# design.net
KiCad netlist of a schematic drawn in Altium Designer
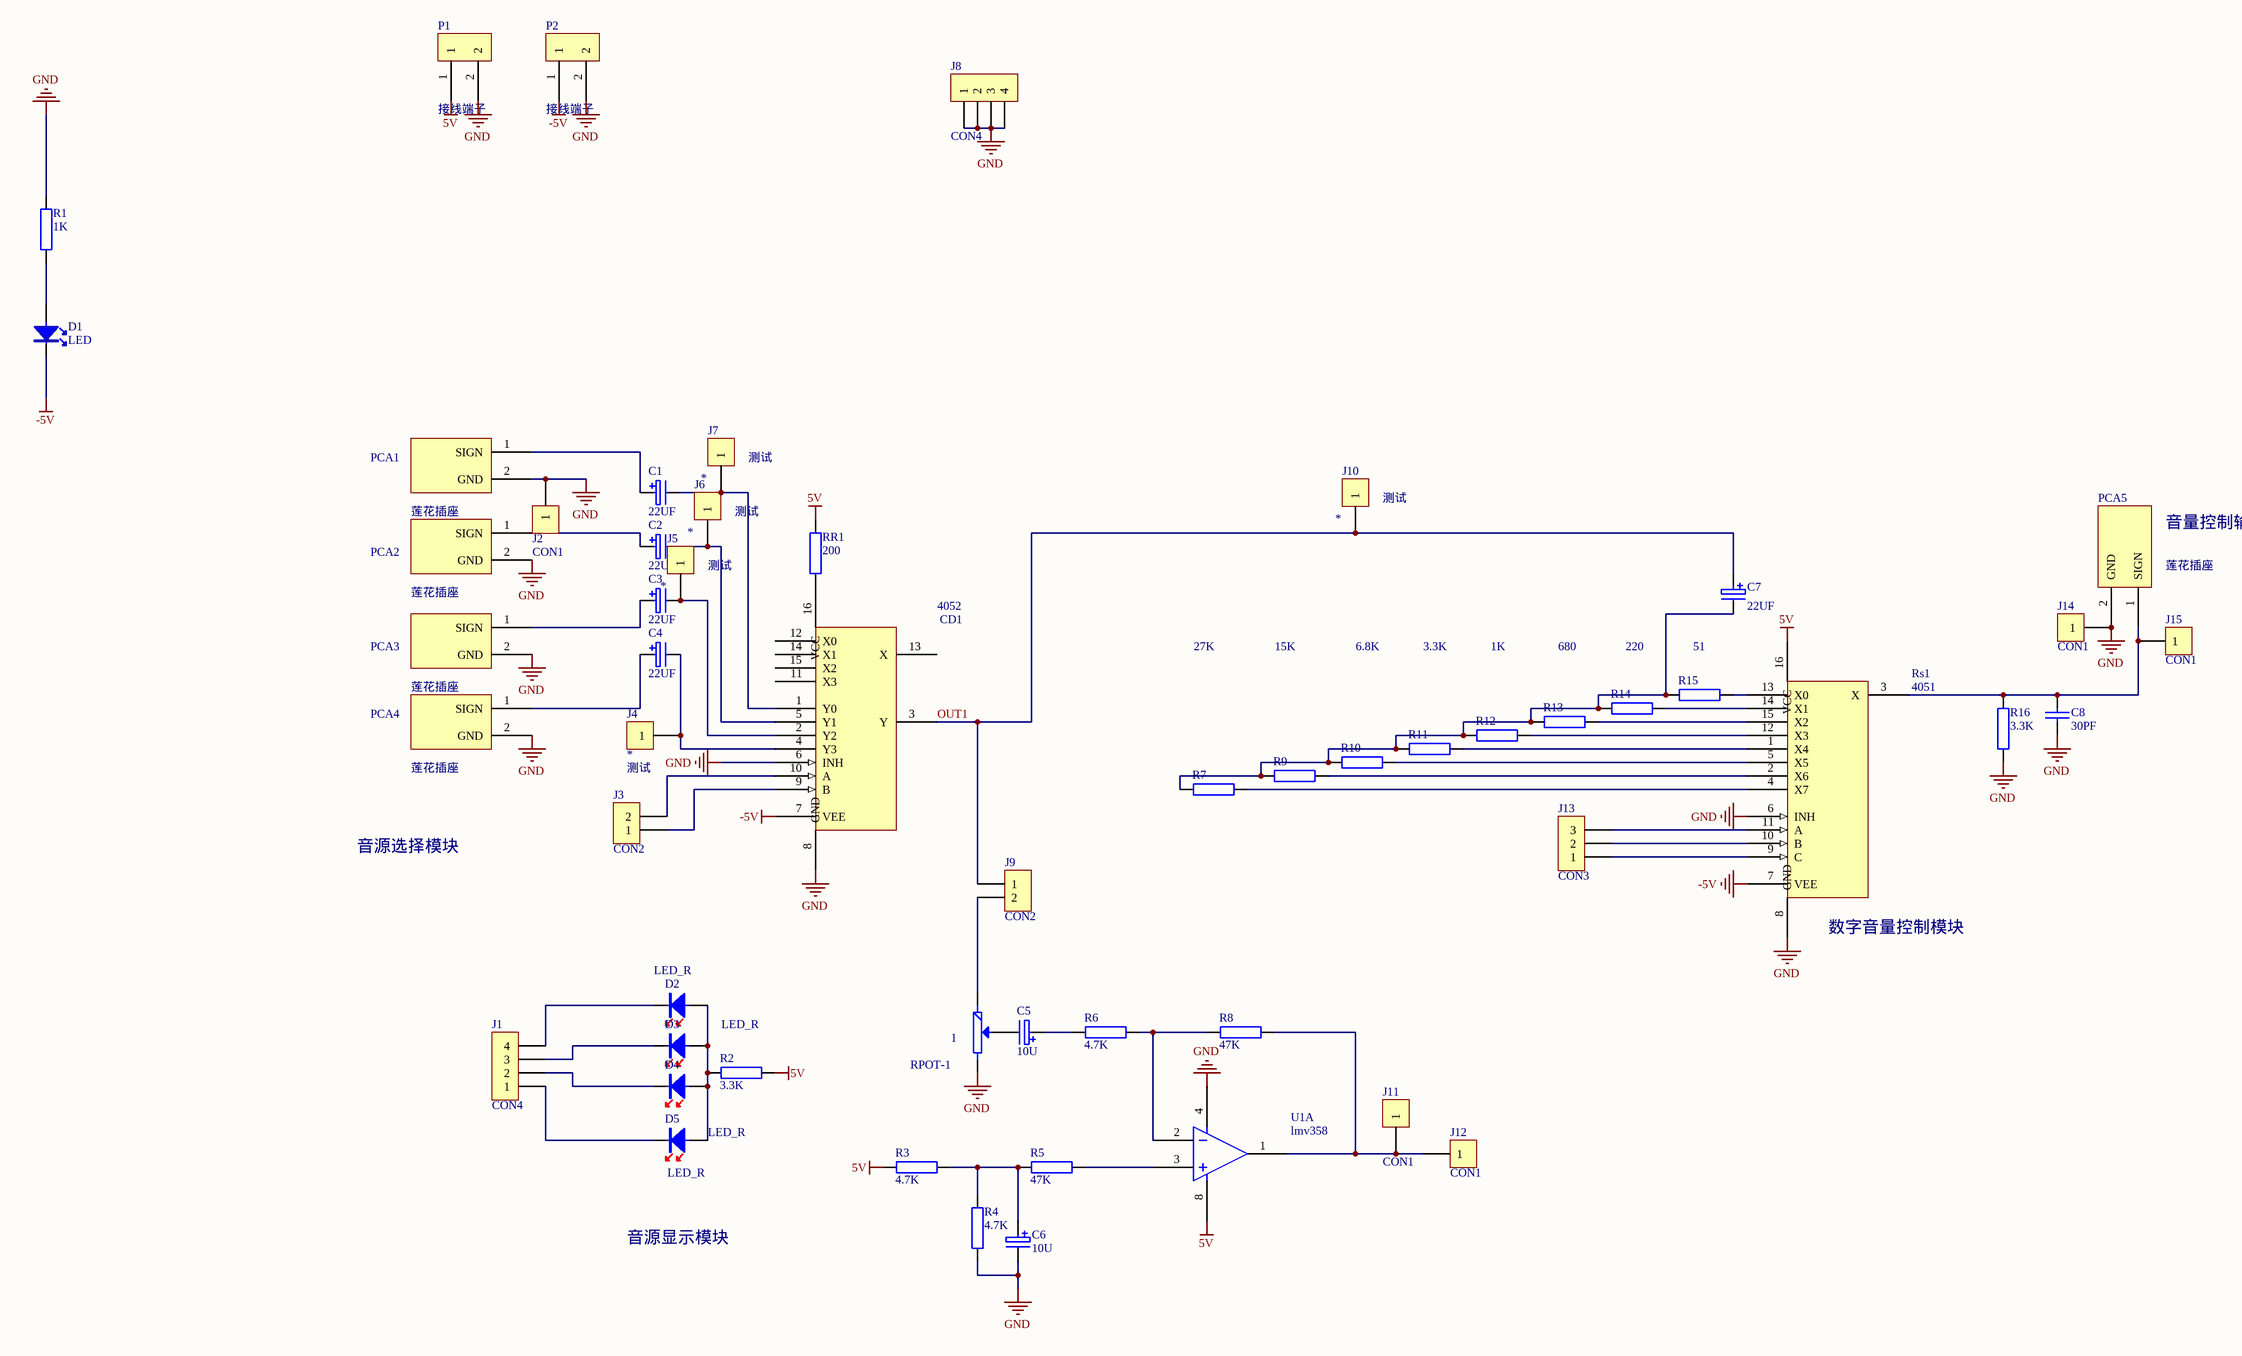
[diagram p0: 开关部分.SchDoc]

(export (version "E")
  (design (tool "Eeschema 10.0.6"))
  (components
    (comp (ref "1")
      (value "RPOT-1")
      (footprint "RVR-2")
      (description "普通电位器")
      (libsource (lib "电阻") (part "RPOT-1"))
    )
    (comp (ref "C1") (value "22UF") (footprint "CAO2") (libsource (lib "电容") (part "CAP3")))
    (comp (ref "C2") (value "22UF") (footprint "CAO2") (libsource (lib "电容") (part "CAP3")))
    (comp (ref "C3") (value "22UF") (footprint "CAO2") (libsource (lib "电容") (part "CAP3")))
    (comp (ref "C4") (value "22UF") (footprint "CAO2") (libsource (lib "电容") (part "CAP3")))
    (comp (ref "C5") (value "10U") (footprint "CAO1") (libsource (lib "电容") (part "CAP3")))
    (comp (ref "C6") (value "10U") (footprint "CAO1") (libsource (lib "电容") (part "CAP3")))
    (comp (ref "C7") (value "22UF") (footprint "CAO2") (libsource (lib "电容") (part "CAP3")))
    (comp (ref "C8") (value "30PF") (footprint "CAP2") (libsource (lib "电容") (part "CAP1")))
    (comp (ref "CD1") (value "4052") (footprint "SO-16") (libsource (lib "51库") (part "4052")))
    (comp (ref "D1") (value "LED") (footprint "LED2_B") (libsource (lib "二极管") (part "LED")))
    (comp (ref "D2") (value "LED_R") (footprint "LED2_B") (libsource (lib "Diode二极管") (part "LED_R")))
    (comp (ref "D3") (value "LED_R") (footprint "LED2_B") (libsource (lib "Diode二极管") (part "LED_R")))
    (comp (ref "D4") (value "LED_R") (footprint "LED2_B") (libsource (lib "Diode二极管") (part "LED_R")))
    (comp (ref "D5") (value "LED_R") (footprint "LED2_B") (libsource (lib "Diode二极管") (part "LED_R")))
    (comp (ref "J1")
      (value "CON4")
      (footprint "sip-4")
      (description "Connector")
      (libsource (lib "") (part "CON4_1"))
    )
    (comp (ref "J2")
      (value "CON1")
      (footprint "SIP-1")
      (description "Connector")
      (libsource (lib "排针") (part "测试"))
    )
    (comp (ref "J3")
      (value "CON2")
      (footprint "sip-2")
      (description "Connector")
      (libsource (lib "排针") (part "CON2"))
    )
    (comp (ref "J4")
      (value "*")
      (footprint "SIP-1")
      (description "Connector")
      (fields (field (name "测试") "测试"))
      (libsource (lib "") (part "CON1_2"))
    )
    (comp (ref "J5")
      (value "*")
      (footprint "SIP-1")
      (description "Connector")
      (fields (field (name "测试") "测试"))
      (libsource (lib "排针") (part "CON1"))
    )
    (comp (ref "J6")
      (value "*")
      (footprint "SIP-1")
      (description "Connector")
      (fields (field (name "测试") "测试"))
      (libsource (lib "排针") (part "CON1"))
    )
    (comp (ref "J7")
      (value "*")
      (footprint "SIP-1")
      (description "Connector")
      (fields (field (name "测试") "测试"))
      (libsource (lib "排针") (part "CON1"))
    )
    (comp (ref "J8")
      (value "CON4")
      (footprint "sip-4")
      (description "Connector")
      (libsource (lib "排针") (part "CON4"))
    )
    (comp (ref "J9")
      (value "CON2")
      (footprint "sip-2")
      (description "Connector")
      (libsource (lib "") (part "CON2_1"))
    )
    (comp (ref "J10")
      (value "*")
      (footprint "SIP-1")
      (description "Connector")
      (fields (field (name "测试") "测试"))
      (libsource (lib "排针") (part "CON1"))
    )
    (comp (ref "J11")
      (value "CON1")
      (footprint "SIP-1")
      (description "Connector")
      (libsource (lib "排针") (part "CON1"))
    )
    (comp (ref "J12")
      (value "CON1")
      (footprint "SIP-1")
      (description "Connector")
      (libsource (lib "") (part "CON1_1"))
    )
    (comp (ref "J13")
      (value "CON3")
      (footprint "sip-3")
      (description "Connector")
      (libsource (lib "排针") (part "CON3"))
    )
    (comp (ref "J14")
      (value "CON1")
      (footprint "SIP-1")
      (description "Connector")
      (libsource (lib "") (part "CON1_2"))
    )
    (comp (ref "J15")
      (value "CON1")
      (footprint "SIP-1")
      (description "Connector")
      (libsource (lib "") (part "CON1_1"))
    )
    (comp (ref "P1") (value "接线端子") (footprint "音频功放自画库:接线端子") (libsource (lib "音频功放自画库") (part "接线端子")))
    (comp (ref "P2") (value "接线端子") (footprint "音频功放自画库:接线端子") (libsource (lib "音频功放自画库") (part "接线端子")))
    (comp (ref "PCA1") (value "莲花插座") (footprint "莲花母座") (libsource (lib "音频功放自画库") (part "PCA")))
    (comp (ref "PCA2") (value "莲花插座") (footprint "莲花母座") (libsource (lib "音频功放自画库") (part "PCA")))
    (comp (ref "PCA3") (value "莲花插座") (footprint "莲花母座") (libsource (lib "音频功放自画库") (part "PCA")))
    (comp (ref "PCA4") (value "莲花插座") (footprint "莲花母座") (libsource (lib "音频功放自画库") (part "PCA")))
    (comp (ref "PCA5") (value "莲花插座") (footprint "莲花母座") (libsource (lib "") (part "PCA_1")))
    (comp (ref "R1")
      (value "1K")
      (footprint "AXIAL0.4")
      (description "电阻")
      (libsource (lib "电阻") (part "RES"))
    )
    (comp (ref "R2")
      (value "3.3K")
      (footprint "AXIAL0.4")
      (description "电阻")
      (libsource (lib "电阻") (part "RES"))
    )
    (comp (ref "R3")
      (value "4.7K")
      (footprint "AXIAL0.4")
      (description "电阻")
      (libsource (lib "电阻") (part "RES"))
    )
    (comp (ref "R4")
      (value "4.7K")
      (footprint "AXIAL0.4")
      (description "电阻")
      (libsource (lib "电阻") (part "RES"))
    )
    (comp (ref "R5")
      (value "47K")
      (footprint "AXIAL0.4")
      (description "电阻")
      (libsource (lib "电阻") (part "RES"))
    )
    (comp (ref "R6")
      (value "4.7K")
      (footprint "AXIAL0.4")
      (description "电阻")
      (libsource (lib "电阻") (part "RES"))
    )
    (comp (ref "R7")
      (value "27K")
      (footprint "AXIAL0.4")
      (description "电阻")
      (libsource (lib "电阻") (part "RES"))
    )
    (comp (ref "R8")
      (value "47K")
      (footprint "AXIAL0.4")
      (description "电阻")
      (libsource (lib "电阻") (part "RES"))
    )
    (comp (ref "R9")
      (value "15K")
      (footprint "AXIAL0.4")
      (description "电阻")
      (libsource (lib "电阻") (part "RES"))
    )
    (comp (ref "R10")
      (value "6.8K")
      (footprint "AXIAL0.4")
      (description "电阻")
      (libsource (lib "电阻") (part "RES"))
    )
    (comp (ref "R11")
      (value "3.3K")
      (footprint "AXIAL0.4")
      (description "电阻")
      (libsource (lib "电阻") (part "RES"))
    )
    (comp (ref "R12")
      (value "1K")
      (footprint "AXIAL0.4")
      (description "电阻")
      (libsource (lib "电阻") (part "RES"))
    )
    (comp (ref "R13")
      (value "680")
      (footprint "AXIAL0.4")
      (description "电阻")
      (libsource (lib "电阻") (part "RES"))
    )
    (comp (ref "R14")
      (value "220")
      (footprint "AXIAL0.4")
      (description "电阻")
      (libsource (lib "电阻") (part "RES"))
    )
    (comp (ref "R15")
      (value "51")
      (footprint "AXIAL0.4")
      (description "电阻")
      (libsource (lib "电阻") (part "RES"))
    )
    (comp (ref "R16")
      (value "3.3K")
      (footprint "AXIAL0.4")
      (description "电阻")
      (libsource (lib "电阻") (part "RES"))
    )
    (comp (ref "RR1")
      (value "200")
      (footprint "AXIAL0.4")
      (description "电阻")
      (libsource (lib "电阻") (part "RES"))
    )
    (comp (ref "Rs1") (value "4051") (footprint "SO-16") (libsource (lib "51库") (part "4051")))
    (comp (ref "U1") (value "lmv358") (footprint "SOP8") (libsource (lib "运放") (part "NE5532")))
  )
  (nets
    (net (code "1") (name "-5V") (class "Default")
      (node (ref "CD1") (pin "7") (pinfunction "VEE_7") (pintype "passive"))
      (node (ref "D1") (pin "2") (pinfunction "2_2") (pintype "passive"))
      (node (ref "P2") (pin "1") (pinfunction "1_1") (pintype "passive"))
      (node (ref "Rs1") (pin "7") (pinfunction "VEE_7") (pintype "passive"))
    )
    (net (code "2") (name "/OUT1") (class "Default")
      (node (ref "C7") (pin "1") (pintype "passive"))
      (node (ref "CD1") (pin "3") (pinfunction "Y_3") (pintype "passive"))
      (node (ref "J10") (pin "1") (pinfunction "1_1") (pintype "passive"))
      (node (ref "J9") (pin "1") (pinfunction "1_1") (pintype "passive"))
    )
    (net (code "3") (name "5V") (class "Default")
      (node (ref "P1") (pin "1") (pinfunction "1_1") (pintype "passive"))
      (node (ref "R2") (pin "1") (pinfunction "1_1") (pintype "passive"))
      (node (ref "R3") (pin "1") (pinfunction "1_1") (pintype "passive"))
      (node (ref "RR1") (pin "1") (pinfunction "1_1") (pintype "passive"))
      (node (ref "Rs1") (pin "16") (pinfunction "VCC_16") (pintype "power_in"))
      (node (ref "U1") (pin "8") (pintype "passive"))
    )
    (net (code "4") (name "GND") (class "Default")
      (node (ref "1") (pin "3") (pinfunction "3_3") (pintype "passive"))
      (node (ref "C6") (pin "2") (pintype "passive"))
      (node (ref "C8") (pin "2") (pinfunction "2_2") (pintype "passive"))
      (node (ref "CD1") (pin "6") (pinfunction "INH_6") (pintype "input"))
      (node (ref "CD1") (pin "8") (pinfunction "GND_8") (pintype "power_in"))
      (node (ref "J14") (pin "1") (pinfunction "1_1") (pintype "passive"))
      (node (ref "J2") (pin "1") (pinfunction "1_1") (pintype "passive"))
      (node (ref "J8") (pin "1") (pinfunction "1_1") (pintype "passive"))
      (node (ref "J8") (pin "2") (pinfunction "2_2") (pintype "passive"))
      (node (ref "J8") (pin "3") (pinfunction "3_3") (pintype "passive"))
      (node (ref "J8") (pin "4") (pinfunction "4_4") (pintype "passive"))
      (node (ref "P1") (pin "2") (pinfunction "2_2") (pintype "passive"))
      (node (ref "P2") (pin "2") (pinfunction "2_2") (pintype "passive"))
      (node (ref "PCA1") (pin "2") (pinfunction "GND_2") (pintype "passive"))
      (node (ref "PCA2") (pin "2") (pinfunction "GND_2") (pintype "passive"))
      (node (ref "PCA3") (pin "2") (pinfunction "GND_2") (pintype "passive"))
      (node (ref "PCA4") (pin "2") (pinfunction "GND_2") (pintype "passive"))
      (node (ref "PCA5") (pin "2") (pinfunction "GND_2") (pintype "passive"))
      (node (ref "R1") (pin "2") (pinfunction "2_2") (pintype "passive"))
      (node (ref "R16") (pin "1") (pinfunction "1_1") (pintype "passive"))
      (node (ref "R4") (pin "1") (pinfunction "1_1") (pintype "passive"))
      (node (ref "Rs1") (pin "6") (pinfunction "INH_6") (pintype "input"))
      (node (ref "Rs1") (pin "8") (pinfunction "GND_8") (pintype "power_in"))
      (node (ref "U1") (pin "4") (pintype "passive"))
    )
    (net (code "5") (name "Net-(1-M)") (class "Default")
      (node (ref "1") (pin "2") (pinfunction "M_2") (pintype "passive"))
      (node (ref "C5") (pin "2") (pintype "passive"))
    )
    (net (code "6") (name "Net-(1-Pad1)") (class "Default")
      (node (ref "1") (pin "1") (pinfunction "1_1") (pintype "passive"))
      (node (ref "J9") (pin "2") (pinfunction "2_2") (pintype "passive"))
    )
    (net (code "7") (name "Net-(C5-Pad1)") (class "Default")
      (node (ref "C5") (pin "1") (pintype "passive"))
      (node (ref "R6") (pin "1") (pinfunction "1_1") (pintype "passive"))
    )
    (net (code "8") (name "Net-(C6-Pad1)") (class "Default")
      (node (ref "C6") (pin "1") (pintype "passive"))
      (node (ref "R3") (pin "2") (pinfunction "2_2") (pintype "passive"))
      (node (ref "R4") (pin "2") (pinfunction "2_2") (pintype "passive"))
      (node (ref "R5") (pin "1") (pinfunction "1_1") (pintype "passive"))
    )
    (net (code "9") (name "Net-(C7-Pad2)") (class "Default")
      (node (ref "C7") (pin "2") (pintype "passive"))
      (node (ref "R10") (pin "1") (pinfunction "1_1") (pintype "passive"))
      (node (ref "R11") (pin "1") (pinfunction "1_1") (pintype "passive"))
      (node (ref "R12") (pin "1") (pinfunction "1_1") (pintype "passive"))
      (node (ref "R13") (pin "1") (pinfunction "1_1") (pintype "passive"))
      (node (ref "R14") (pin "1") (pinfunction "1_1") (pintype "passive"))
      (node (ref "R15") (pin "1") (pinfunction "1_1") (pintype "passive"))
      (node (ref "R7") (pin "1") (pinfunction "1_1") (pintype "passive"))
      (node (ref "R9") (pin "1") (pinfunction "1_1") (pintype "passive"))
    )
    (net (code "10") (name "Net-(CD1-A)") (class "Default")
      (node (ref "CD1") (pin "10") (pinfunction "A_10") (pintype "input"))
      (node (ref "J3") (pin "2") (pinfunction "2_2") (pintype "passive"))
    )
    (net (code "11") (name "Net-(CD1-B)") (class "Default")
      (node (ref "CD1") (pin "9") (pinfunction "B_9") (pintype "input"))
      (node (ref "J3") (pin "1") (pinfunction "1_1") (pintype "passive"))
    )
    (net (code "12") (name "Net-(CD1-VCC)") (class "Default")
      (node (ref "CD1") (pin "16") (pinfunction "VCC_16") (pintype "power_in"))
      (node (ref "RR1") (pin "2") (pinfunction "2_2") (pintype "passive"))
    )
    (net (code "13") (name "Net-(CD1-Y0)") (class "Default")
      (node (ref "C1") (pin "2") (pintype "passive"))
      (node (ref "CD1") (pin "1") (pinfunction "Y0_1") (pintype "passive"))
      (node (ref "J7") (pin "1") (pinfunction "1_1") (pintype "passive"))
    )
    (net (code "14") (name "Net-(CD1-Y1)") (class "Default")
      (node (ref "C2") (pin "2") (pintype "passive"))
      (node (ref "CD1") (pin "5") (pinfunction "Y1_5") (pintype "passive"))
      (node (ref "J6") (pin "1") (pinfunction "1_1") (pintype "passive"))
    )
    (net (code "15") (name "Net-(CD1-Y2)") (class "Default")
      (node (ref "C3") (pin "2") (pintype "passive"))
      (node (ref "CD1") (pin "2") (pinfunction "Y2_2") (pintype "passive"))
      (node (ref "J5") (pin "1") (pinfunction "1_1") (pintype "passive"))
    )
    (net (code "16") (name "Net-(CD1-Y3)") (class "Default")
      (node (ref "C4") (pin "2") (pintype "passive"))
      (node (ref "CD1") (pin "4") (pinfunction "Y3_4") (pintype "passive"))
      (node (ref "J4") (pin "1") (pinfunction "1_1") (pintype "passive"))
    )
    (net (code "17") (name "Net-(D1-Pad1)") (class "Default")
      (node (ref "D1") (pin "1") (pinfunction "1_1") (pintype "passive"))
      (node (ref "R1") (pin "1") (pinfunction "1_1") (pintype "passive"))
    )
    (net (code "18") (name "Net-(D2-Pad1)") (class "Default")
      (node (ref "D2") (pin "1") (pinfunction "1_1") (pintype "passive"))
      (node (ref "D3") (pin "1") (pinfunction "1_1") (pintype "passive"))
      (node (ref "D4") (pin "1") (pinfunction "1_1") (pintype "passive"))
      (node (ref "D5") (pin "1") (pinfunction "1_1") (pintype "passive"))
      (node (ref "R2") (pin "2") (pinfunction "2_2") (pintype "passive"))
    )
    (net (code "19") (name "Net-(D2-Pad2)") (class "Default")
      (node (ref "D2") (pin "2") (pinfunction "2_2") (pintype "passive"))
      (node (ref "J1") (pin "4") (pinfunction "4_4") (pintype "passive"))
    )
    (net (code "20") (name "Net-(D3-Pad2)") (class "Default")
      (node (ref "D3") (pin "2") (pinfunction "2_2") (pintype "passive"))
      (node (ref "J1") (pin "3") (pinfunction "3_3") (pintype "passive"))
    )
    (net (code "21") (name "Net-(D4-Pad2)") (class "Default")
      (node (ref "D4") (pin "2") (pinfunction "2_2") (pintype "passive"))
      (node (ref "J1") (pin "2") (pinfunction "2_2") (pintype "passive"))
    )
    (net (code "22") (name "Net-(D5-Pad2)") (class "Default")
      (node (ref "D5") (pin "2") (pinfunction "2_2") (pintype "passive"))
      (node (ref "J1") (pin "1") (pinfunction "1_1") (pintype "passive"))
    )
    (net (code "23") (name "Net-(J11-Pad1)") (class "Default")
      (node (ref "J11") (pin "1") (pinfunction "1_1") (pintype "passive"))
      (node (ref "J12") (pin "1") (pinfunction "1_1") (pintype "passive"))
      (node (ref "R8") (pin "2") (pinfunction "2_2") (pintype "passive"))
      (node (ref "U1") (pin "1") (pintype "passive"))
    )
    (net (code "24") (name "Net-(PCA1-SIGN)") (class "Default")
      (node (ref "C1") (pin "1") (pintype "passive"))
      (node (ref "PCA1") (pin "1") (pinfunction "SIGN_1") (pintype "passive"))
    )
    (net (code "25") (name "Net-(PCA2-SIGN)") (class "Default")
      (node (ref "C2") (pin "1") (pintype "passive"))
      (node (ref "PCA2") (pin "1") (pinfunction "SIGN_1") (pintype "passive"))
    )
    (net (code "26") (name "Net-(PCA3-SIGN)") (class "Default")
      (node (ref "C3") (pin "1") (pintype "passive"))
      (node (ref "PCA3") (pin "1") (pinfunction "SIGN_1") (pintype "passive"))
    )
    (net (code "27") (name "Net-(PCA4-SIGN)") (class "Default")
      (node (ref "C4") (pin "1") (pintype "passive"))
      (node (ref "PCA4") (pin "1") (pinfunction "SIGN_1") (pintype "passive"))
    )
    (net (code "28") (name "Net-(PCA5-SIGN)") (class "Default")
      (node (ref "C8") (pin "1") (pinfunction "1_1") (pintype "passive"))
      (node (ref "J15") (pin "1") (pinfunction "1_1") (pintype "passive"))
      (node (ref "PCA5") (pin "1") (pinfunction "SIGN_1") (pintype "passive"))
      (node (ref "R16") (pin "2") (pinfunction "2_2") (pintype "passive"))
      (node (ref "Rs1") (pin "3") (pinfunction "X_3") (pintype "passive"))
    )
    (net (code "29") (name "Net-(R5-Pad2)") (class "Default")
      (node (ref "R5") (pin "2") (pinfunction "2_2") (pintype "passive"))
      (node (ref "U1") (pin "3") (pintype "passive"))
    )
    (net (code "30") (name "Net-(R6-Pad2)") (class "Default")
      (node (ref "R6") (pin "2") (pinfunction "2_2") (pintype "passive"))
      (node (ref "R8") (pin "1") (pinfunction "1_1") (pintype "passive"))
      (node (ref "U1") (pin "2") (pintype "passive"))
    )
    (net (code "31") (name "Net-(Rs1-A)") (class "Default")
      (node (ref "J13") (pin "3") (pinfunction "3_3") (pintype "passive"))
      (node (ref "Rs1") (pin "11") (pinfunction "A_11") (pintype "input"))
    )
    (net (code "32") (name "Net-(Rs1-B)") (class "Default")
      (node (ref "J13") (pin "2") (pinfunction "2_2") (pintype "passive"))
      (node (ref "Rs1") (pin "10") (pinfunction "B_10") (pintype "input"))
    )
    (net (code "33") (name "Net-(Rs1-C)") (class "Default")
      (node (ref "J13") (pin "1") (pinfunction "1_1") (pintype "passive"))
      (node (ref "Rs1") (pin "9") (pinfunction "C_9") (pintype "input"))
    )
    (net (code "34") (name "Net-(Rs1-X0)") (class "Default")
      (node (ref "R15") (pin "2") (pinfunction "2_2") (pintype "passive"))
      (node (ref "Rs1") (pin "13") (pinfunction "X0_13") (pintype "passive"))
    )
    (net (code "35") (name "Net-(Rs1-X1)") (class "Default")
      (node (ref "R14") (pin "2") (pinfunction "2_2") (pintype "passive"))
      (node (ref "Rs1") (pin "14") (pinfunction "X1_14") (pintype "passive"))
    )
    (net (code "36") (name "Net-(Rs1-X2)") (class "Default")
      (node (ref "R13") (pin "2") (pinfunction "2_2") (pintype "passive"))
      (node (ref "Rs1") (pin "15") (pinfunction "X2_15") (pintype "passive"))
    )
    (net (code "37") (name "Net-(Rs1-X3)") (class "Default")
      (node (ref "R12") (pin "2") (pinfunction "2_2") (pintype "passive"))
      (node (ref "Rs1") (pin "12") (pinfunction "X3_12") (pintype "passive"))
    )
    (net (code "38") (name "Net-(Rs1-X4)") (class "Default")
      (node (ref "R11") (pin "2") (pinfunction "2_2") (pintype "passive"))
      (node (ref "Rs1") (pin "1") (pinfunction "X4_1") (pintype "passive"))
    )
    (net (code "39") (name "Net-(Rs1-X5)") (class "Default")
      (node (ref "R10") (pin "2") (pinfunction "2_2") (pintype "passive"))
      (node (ref "Rs1") (pin "5") (pinfunction "X5_5") (pintype "passive"))
    )
    (net (code "40") (name "Net-(Rs1-X6)") (class "Default")
      (node (ref "R9") (pin "2") (pinfunction "2_2") (pintype "passive"))
      (node (ref "Rs1") (pin "2") (pinfunction "X6_2") (pintype "passive"))
    )
    (net (code "41") (name "Net-(Rs1-X7)") (class "Default")
      (node (ref "R7") (pin "2") (pinfunction "2_2") (pintype "passive"))
      (node (ref "Rs1") (pin "4") (pinfunction "X7_4") (pintype "passive"))
    )
    (net (code "42") (name "unconnected-(CD1-X-Pad13)") (class "Default")
      (node (ref "CD1") (pin "13") (pinfunction "X_13") (pintype "passive"))
    )
    (net (code "43") (name "unconnected-(CD1-X0-Pad12)") (class "Default")
      (node (ref "CD1") (pin "12") (pinfunction "X0_12") (pintype "passive"))
    )
    (net (code "44") (name "unconnected-(CD1-X1-Pad14)") (class "Default")
      (node (ref "CD1") (pin "14") (pinfunction "X1_14") (pintype "passive"))
    )
    (net (code "45") (name "unconnected-(CD1-X2-Pad15)") (class "Default")
      (node (ref "CD1") (pin "15") (pinfunction "X2_15") (pintype "passive"))
    )
    (net (code "46") (name "unconnected-(CD1-X3-Pad11)") (class "Default")
      (node (ref "CD1") (pin "11") (pinfunction "X3_11") (pintype "passive"))
    )
  )
)
